# SparkFun_Thermocouple_Breakout.net
KiCad netlist of a schematic drawn in EAGLE
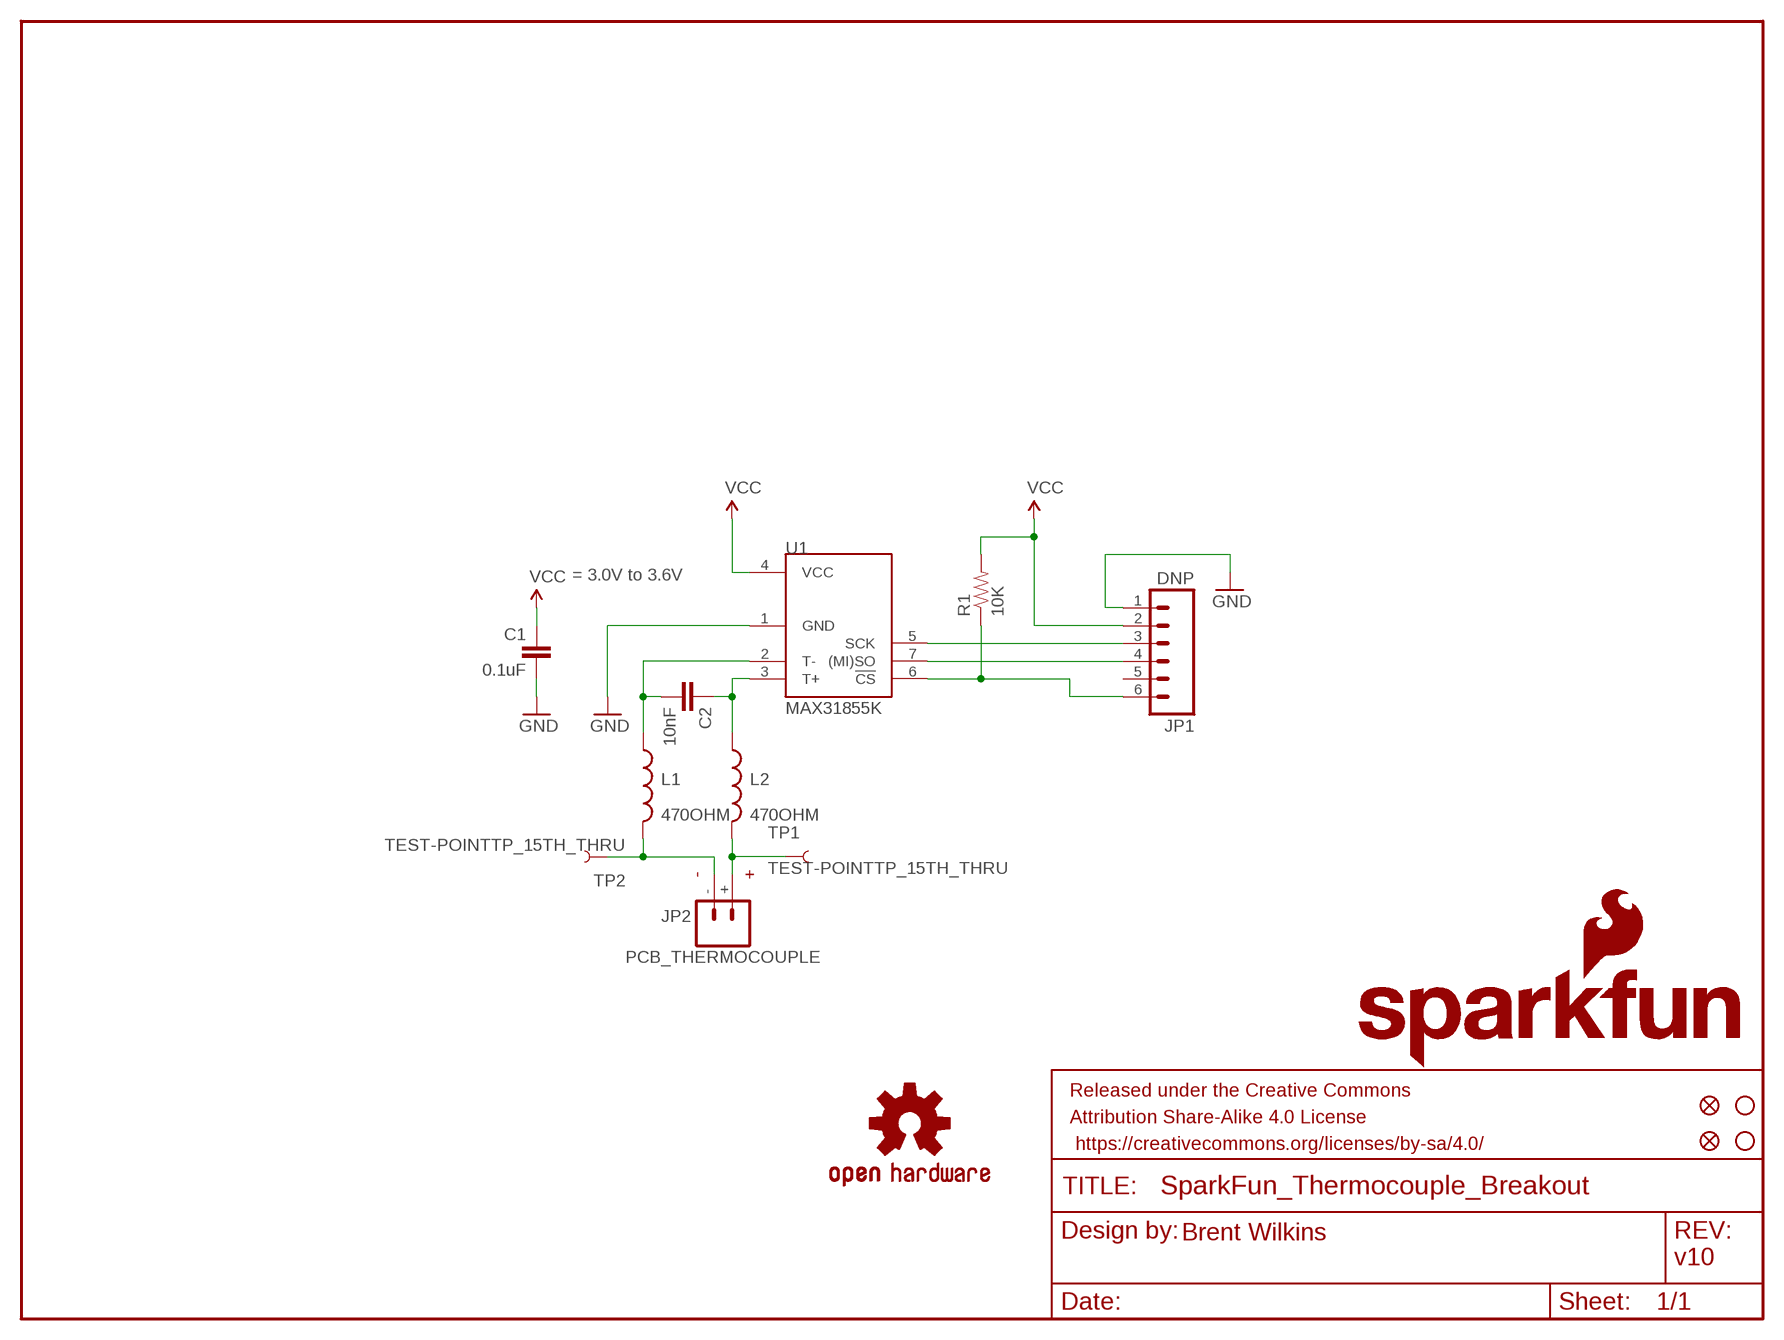
[diagram p0: schematic, sheet 1]

(export (version "E")
  (design (tool "Eeschema 10.0.6"))
  (components
    (comp (ref "C1")
      (value "0.1uF")
      (footprint "eagle-import:0603-CAP")
      (libsource (lib "eagle-import") (part "0.1UF-25V(+80/-20%)(0603)"))
    )
    (comp (ref "C2")
      (value "10nF")
      (footprint "eagle-import:0603-CAP")
      (libsource (lib "eagle-import") (part "10NF/10000PF-50V-10%(0603)"))
    )
    (comp (ref "FID1")
      (value "FIDUCIAL1X2")
      (footprint "eagle-import:FIDUCIAL-1X2")
      (libsource (lib "eagle-import") (part "FIDUCIAL1X2"))
    )
    (comp (ref "FID2")
      (value "FIDUCIAL1X2")
      (footprint "eagle-import:FIDUCIAL-1X2")
      (libsource (lib "eagle-import") (part "FIDUCIAL1X2"))
    )
    (comp (ref "FRAME1")
      (value ">VERSION")
      (footprint "eagle-import:CREATIVE_COMMONS")
      (fields (field (name "DESIGNER") "Brent Wilkins"))
      (libsource (lib "eagle-import") (part "FRAME-LETTER"))
    )
    (comp (ref "JP1")
      (value "DNP")
      (footprint "eagle-import:1X06")
      (libsource (lib "eagle-import") (part "M06SILK_FEMALE_PTH"))
    )
    (comp (ref "JP2")
      (value "PCB_THERMOCOUPLE")
      (footprint "eagle-import:PCC-SMP")
      (libsource (lib "eagle-import") (part "PCB_THERMOCOUPLE"))
    )
    (comp (ref "L1")
      (value "470OHM")
      (footprint "eagle-import:0603")
      (libsource (lib "eagle-import") (part "INDUCTOR0603"))
    )
    (comp (ref "L2")
      (value "470OHM")
      (footprint "eagle-import:0603")
      (libsource (lib "eagle-import") (part "INDUCTOR0603"))
    )
    (comp (ref "LOGO1")
      (value "OSHW-LOGOS")
      (footprint "eagle-import:OSHW-LOGO-S")
      (libsource (lib "eagle-import") (part "OSHW-LOGOS"))
    )
    (comp (ref "LOGO2")
      (value "SFE_LOGO_NAME_FLAME.1_INCH")
      (footprint "eagle-import:SFE_LOGO_NAME_FLAME_.1")
      (libsource (lib "eagle-import") (part "SFE_LOGO_NAME_FLAME.1_INCH"))
    )
    (comp (ref "LOGO3")
      (value "SFE_LOGO_NAME_FLAME.1_INCH")
      (footprint "eagle-import:SFE_LOGO_NAME_FLAME_.1")
      (libsource (lib "eagle-import") (part "SFE_LOGO_NAME_FLAME.1_INCH"))
    )
    (comp (ref "LOGO4")
      (value "OSHW-LOGOS")
      (footprint "eagle-import:OSHW-LOGO-S")
      (libsource (lib "eagle-import") (part "OSHW-LOGOS"))
    )
    (comp (ref "R1")
      (value "10K")
      (footprint "eagle-import:0603-RES")
      (libsource (lib "eagle-import") (part "10KOHM-1/10W-1%(0603)0603"))
    )
    (comp (ref "STANDOFF1")
      (value "STAND-OFF")
      (footprint "eagle-import:STAND-OFF")
      (libsource (lib "eagle-import") (part "STAND-OFF"))
    )
    (comp (ref "STANDOFF4")
      (value "STAND-OFF")
      (footprint "eagle-import:STAND-OFF")
      (libsource (lib "eagle-import") (part "STAND-OFF"))
    )
    (comp (ref "TP1")
      (value "TEST-POINTTP_15TH_THRU")
      (footprint "eagle-import:TP_15TH")
      (libsource (lib "eagle-import") (part "TEST-POINTTP_15TH_THRU"))
    )
    (comp (ref "TP2")
      (value "TEST-POINTTP_15TH_THRU")
      (footprint "eagle-import:TP_15TH")
      (libsource (lib "eagle-import") (part "TEST-POINTTP_15TH_THRU"))
    )
    (comp (ref "U1")
      (value "MAX31855K")
      (footprint "eagle-import:SOIC8")
      (libsource (lib "eagle-import") (part "MAX31855K"))
    )
  )
  (nets
    (net (code "1") (name "GND") (class "Default")
      (node (ref "C1") (pin "2") (pinfunction "2_2") (pintype "passive"))
      (node (ref "JP1") (pin "1") (pinfunction "1_1") (pintype "passive"))
      (node (ref "U1") (pin "1") (pinfunction "GND_1") (pintype "bidirectional"))
    )
    (net (code "2") (name "Net-(TP1-1)") (class "Default")
      (node (ref "JP2") (pin "+") (pinfunction "+_+") (pintype "passive"))
      (node (ref "L2") (pin "2") (pinfunction "2_2") (pintype "passive"))
      (node (ref "TP1") (pin "P$1") (pinfunction "1_P$1") (pintype "bidirectional"))
    )
    (net (code "3") (name "Net-(TP2-1)") (class "Default")
      (node (ref "JP2") (pin "-") (pinfunction "-_-") (pintype "passive"))
      (node (ref "L1") (pin "2") (pinfunction "2_2") (pintype "passive"))
      (node (ref "TP2") (pin "P$1") (pinfunction "1_P$1") (pintype "bidirectional"))
    )
    (net (code "4") (name "Net-(U1-(MI)SO)") (class "Default")
      (node (ref "JP1") (pin "4") (pinfunction "4_4") (pintype "passive"))
      (node (ref "U1") (pin "7") (pinfunction "(MI)SO_7") (pintype "bidirectional"))
    )
    (net (code "5") (name "Net-(U1-SCK)") (class "Default")
      (node (ref "JP1") (pin "3") (pinfunction "3_3") (pintype "passive"))
      (node (ref "U1") (pin "5") (pinfunction "SCK_5") (pintype "bidirectional"))
    )
    (net (code "6") (name "Net-(U1-T+)") (class "Default")
      (node (ref "C2") (pin "1") (pinfunction "1_1") (pintype "passive"))
      (node (ref "L2") (pin "1") (pinfunction "1_1") (pintype "passive"))
      (node (ref "U1") (pin "3") (pinfunction "T+_3") (pintype "bidirectional"))
    )
    (net (code "7") (name "Net-(U1-T-)") (class "Default")
      (node (ref "C2") (pin "2") (pinfunction "2_2") (pintype "passive"))
      (node (ref "L1") (pin "1") (pinfunction "1_1") (pintype "passive"))
      (node (ref "U1") (pin "2") (pinfunction "T-_2") (pintype "bidirectional"))
    )
    (net (code "8") (name "Net-(U1-~{CS})") (class "Default")
      (node (ref "JP1") (pin "6") (pinfunction "6_6") (pintype "passive"))
      (node (ref "R1") (pin "1") (pinfunction "1_1") (pintype "passive"))
      (node (ref "U1") (pin "6") (pinfunction "~{CS}_6") (pintype "bidirectional"))
    )
    (net (code "9") (name "VCC") (class "Default")
      (node (ref "C1") (pin "1") (pinfunction "1_1") (pintype "passive"))
      (node (ref "JP1") (pin "2") (pinfunction "2_2") (pintype "passive"))
      (node (ref "R1") (pin "2") (pinfunction "2_2") (pintype "passive"))
      (node (ref "U1") (pin "4") (pinfunction "VCC_4") (pintype "bidirectional"))
    )
    (net (code "10") (name "unconnected-(JP1-Pad5)") (class "Default")
      (node (ref "JP1") (pin "5") (pinfunction "5_5") (pintype "passive"))
    )
  )
)
